# Fri3d_2026_Keeb_00.net
KiCad netlist of a schematic drawn in Altium Designer
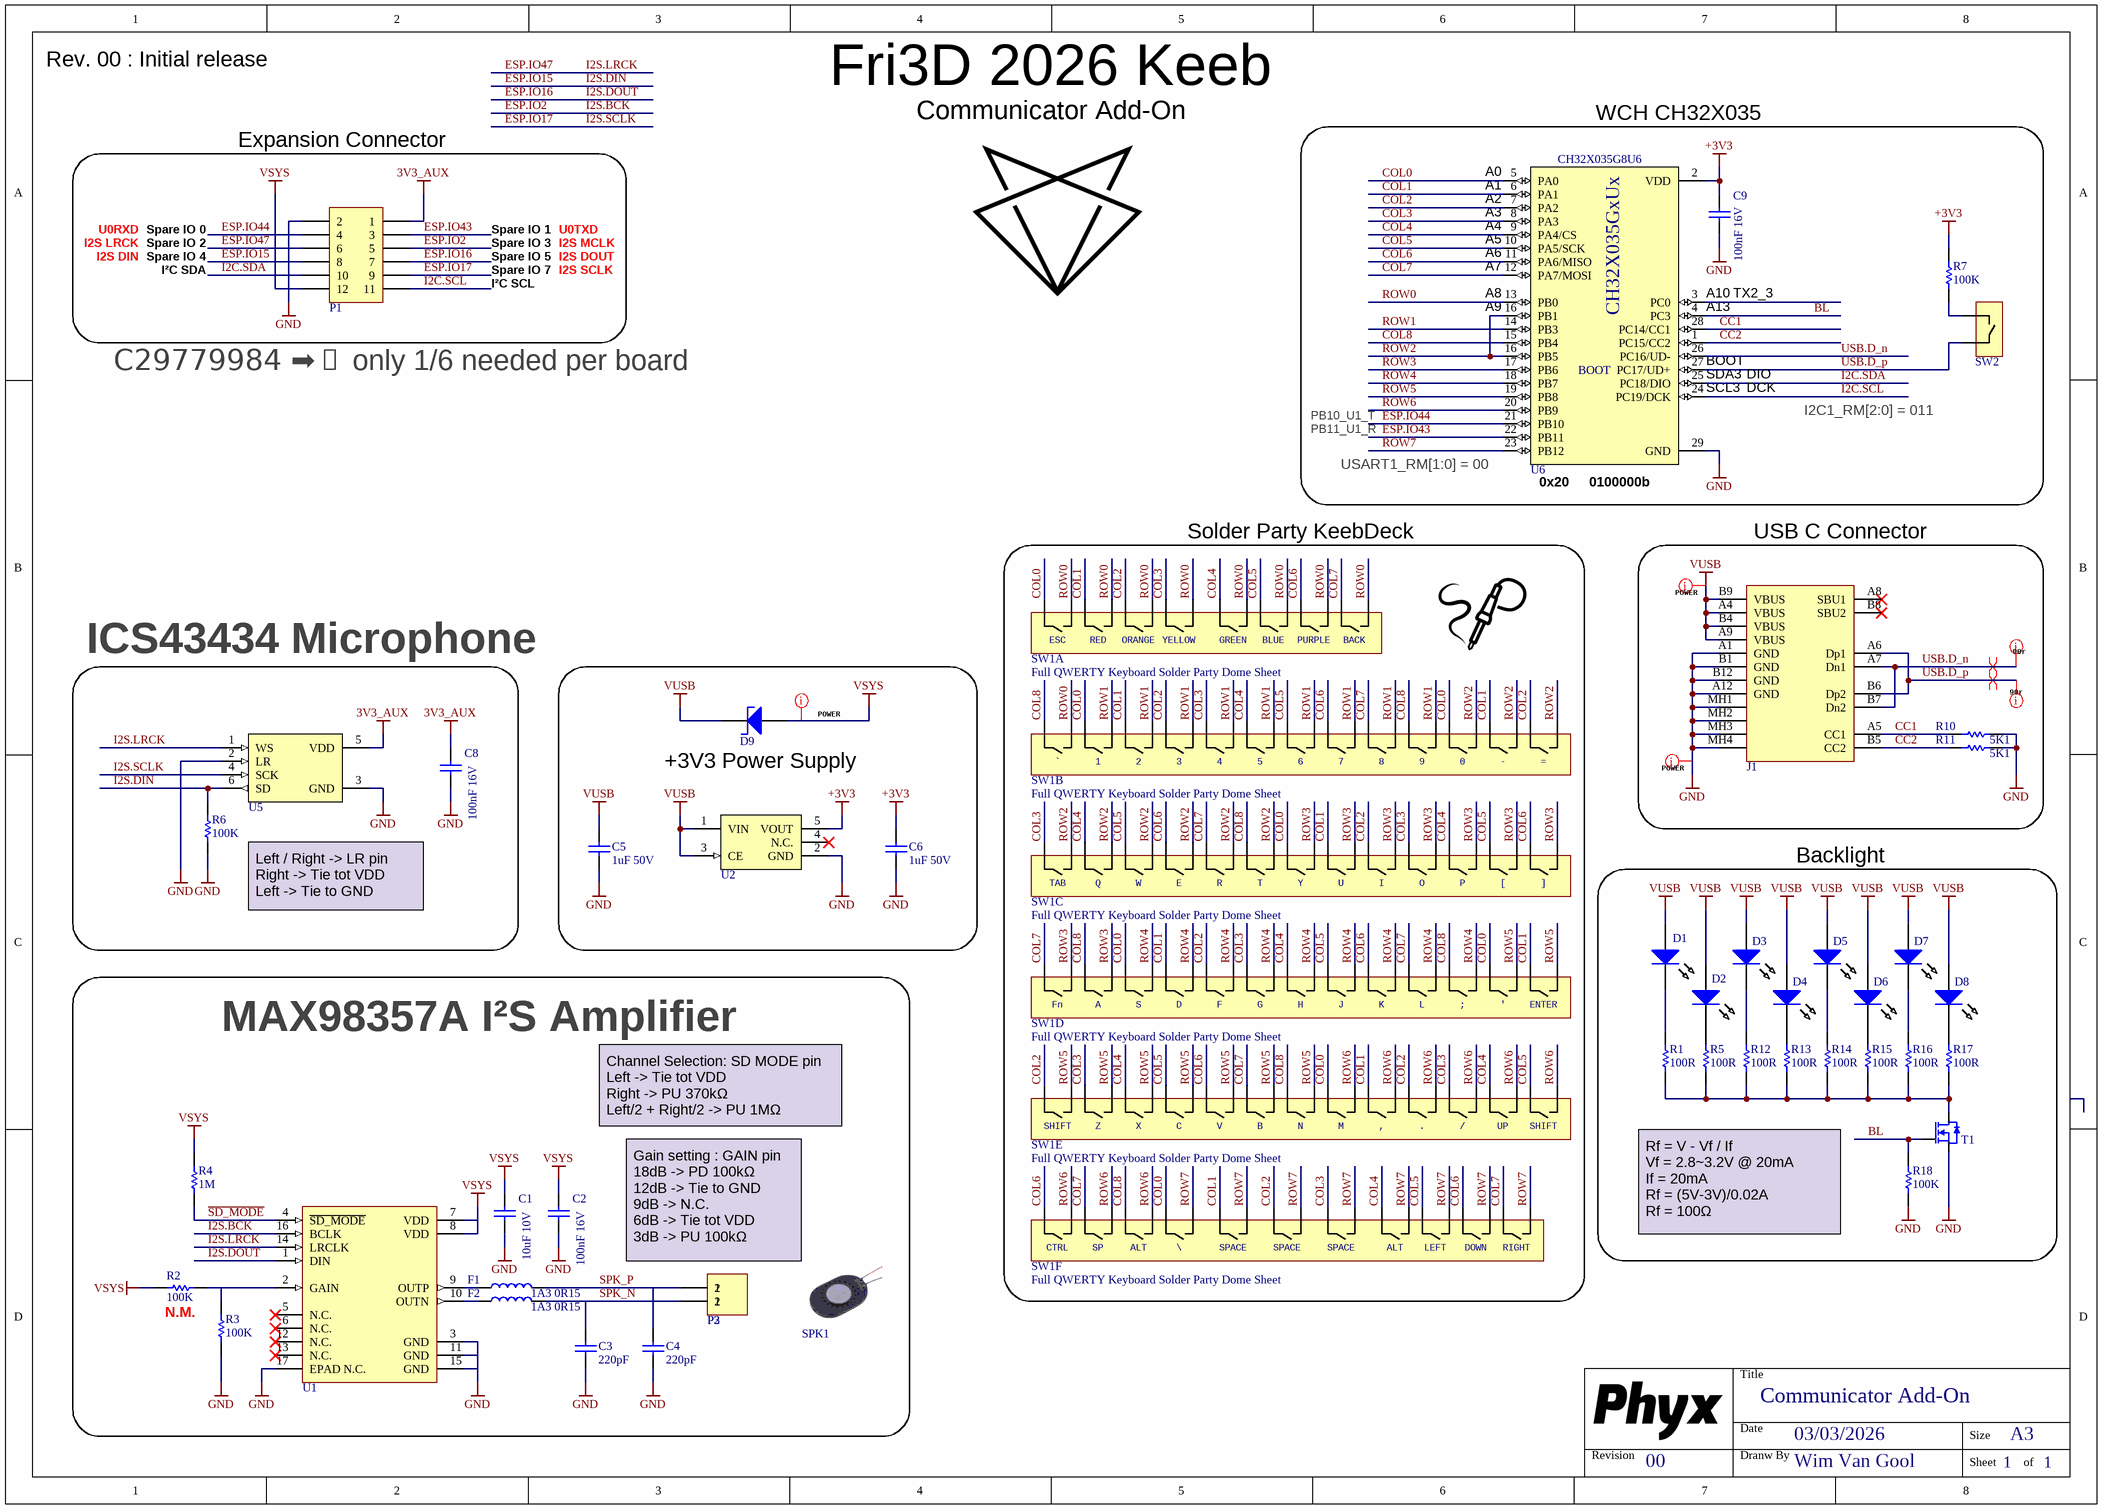
[diagram p0: Fri3d_2026_Keeb_00.SchDoc]

(export (version "E")
  (design (tool "Eeschema 10.0.6"))
  (components
    (comp (ref "C1")
      (value "10uF 10V")
      (footprint "C0805_N")
      (description "Capacitor Ceramic")
      (fields (field (name "Comment") "CAP_CERAMIC"))
      (libsource (lib "Phyx_Components") (part "CAP_CERAMIC"))
    )
    (comp (ref "C2")
      (value "100nF 16V")
      (footprint "C0603_N")
      (description "Capacitor Ceramic")
      (libsource (lib "Phyx_Components") (part "CAP_CERAMIC"))
    )
    (comp (ref "C3")
      (value "220pF")
      (footprint "C0603_N")
      (description "Capacitor Ceramic")
      (fields (field (name "Comment") "CAP_CERAMIC"))
      (libsource (lib "Phyx_Components") (part "CAP_CERAMIC"))
    )
    (comp (ref "C4")
      (value "220pF")
      (footprint "C0603_N")
      (description "Capacitor Ceramic")
      (fields (field (name "Comment") "CAP_CERAMIC"))
      (libsource (lib "Phyx_Components") (part "CAP_CERAMIC"))
    )
    (comp (ref "C5")
      (value "1uF 50V")
      (footprint "C0603_N")
      (description "Capacitor Ceramic")
      (fields (field (name "Comment") "CAP_CERAMIC"))
      (libsource (lib "Phyx_Components") (part "CAP_CERAMIC"))
    )
    (comp (ref "C6")
      (value "1uF 50V")
      (footprint "C0603_N")
      (description "Capacitor Ceramic")
      (fields (field (name "Comment") "CAP_CERAMIC"))
      (libsource (lib "Phyx_Components") (part "CAP_CERAMIC"))
    )
    (comp (ref "C8")
      (value "100nF 16V")
      (footprint "C0603_N")
      (description "Capacitor Ceramic")
      (libsource (lib "Phyx_Components") (part "CAP_CERAMIC"))
    )
    (comp (ref "C9")
      (value "100nF 16V")
      (footprint "C0603_N")
      (description "Capacitor Ceramic")
      (libsource (lib "Phyx_Components") (part "CAP_CERAMIC"))
    )
    (comp (ref "D1")
      (value "Side emitting Cool White LED 3.0V 30mA 120° 2900mcd")
      (footprint "LITE_LTW-010DCG")
      (description "=Description")
      (libsource (lib "Phyx_Components") (part "LED_WHITE"))
    )
    (comp (ref "D2")
      (value "Side emitting Cool White LED 3.0V 30mA 120° 2900mcd")
      (footprint "LITE_LTW-010DCG")
      (description "=Description")
      (libsource (lib "Phyx_Components") (part "LED_WHITE"))
    )
    (comp (ref "D3")
      (value "Side emitting Cool White LED 3.0V 30mA 120° 2900mcd")
      (footprint "LITE_LTW-010DCG")
      (description "=Description")
      (libsource (lib "Phyx_Components") (part "LED_WHITE"))
    )
    (comp (ref "D4")
      (value "Side emitting Cool White LED 3.0V 30mA 120° 2900mcd")
      (footprint "LITE_LTW-010DCG")
      (description "=Description")
      (libsource (lib "Phyx_Components") (part "LED_WHITE"))
    )
    (comp (ref "D5")
      (value "Side emitting Cool White LED 3.0V 30mA 120° 2900mcd")
      (footprint "LITE_LTW-010DCG")
      (description "=Description")
      (libsource (lib "Phyx_Components") (part "LED_WHITE"))
    )
    (comp (ref "D6")
      (value "Side emitting Cool White LED 3.0V 30mA 120° 2900mcd")
      (footprint "LITE_LTW-010DCG")
      (description "=Description")
      (libsource (lib "Phyx_Components") (part "LED_WHITE"))
    )
    (comp (ref "D7")
      (value "Side emitting Cool White LED 3.0V 30mA 120° 2900mcd")
      (footprint "LITE_LTW-010DCG")
      (description "=Description")
      (libsource (lib "Phyx_Components") (part "LED_WHITE"))
    )
    (comp (ref "D8")
      (value "Side emitting Cool White LED 3.0V 30mA 120° 2900mcd")
      (footprint "LITE_LTW-010DCG")
      (description "=Description")
      (libsource (lib "Phyx_Components") (part "LED_WHITE"))
    )
    (comp (ref "D9")
      (value "CUS10S30 Schottky Power Rectifier, 1A, 30V")
      (footprint "SOD-323_AC")
      (description "=Description")
      (libsource (lib "Phyx_Components") (part "Schottky_AC"))
    )
    (comp (ref "F1")
      (value "1A3 0R15")
      (footprint "L0603")
      (fields (field (name "Comment") "BLM18KG601SN1D"))
      (libsource (lib "Phyx_Components") (part "FERRITE"))
    )
    (comp (ref "F2")
      (value "1A3 0R15")
      (footprint "L0603")
      (fields (field (name "Comment") "BLM18KG601SN1D"))
      (libsource (lib "Phyx_Components") (part "FERRITE"))
    )
    (comp (ref "J1")
      (value "USB 2.0 C Reversible Receptacle Horizontal full SMD")
      (footprint "XUNPU-TYPEC-304S-ACP16")
      (libsource (lib "Phyx_Components") (part "USB_C_16_4"))
    )
    (comp (ref "P1")
      (value "Header 6X2")
      (footprint "HDR2X6")
      (libsource (lib "Phyx_Components") (part "Header 6X2"))
    )
    (comp (ref "P2")
      (value "Header 2.0mm Shrouded 2")
      (footprint "WE_620102131822")
      (libsource (lib "Phyx_Components") (part "Header 2"))
    )
    (comp (ref "P3") (value "Header 2 RA") (footprint "HDR1X2_RA") (libsource (lib "") (part "Header 2_1")))
    (comp (ref "R1")
      (value "100R")
      (footprint "R0603_N")
      (fields (field (name "Comment") "RESISTOR"))
      (libsource (lib "Phyx_Components") (part "RESISTOR"))
    )
    (comp (ref "R2")
      (value "100K")
      (footprint "R0603_N")
      (fields (field (name "Comment") "RESISTOR"))
      (libsource (lib "Phyx_Components") (part "RESISTOR"))
    )
    (comp (ref "R3")
      (value "100K")
      (footprint "R0603_N")
      (fields (field (name "Comment") "RESISTOR"))
      (libsource (lib "Phyx_Components") (part "RESISTOR"))
    )
    (comp (ref "R4")
      (value "1M")
      (footprint "R0603_N")
      (fields (field (name "Comment") "RESISTOR"))
      (libsource (lib "Phyx_Components") (part "RESISTOR"))
    )
    (comp (ref "R5")
      (value "100R")
      (footprint "R0603_N")
      (fields (field (name "Comment") "RESISTOR"))
      (libsource (lib "Phyx_Components") (part "RESISTOR"))
    )
    (comp (ref "R6")
      (value "100K")
      (footprint "R0603_N")
      (fields (field (name "Comment") "RESISTOR"))
      (libsource (lib "Phyx_Components") (part "RESISTOR"))
    )
    (comp (ref "R7")
      (value "100K")
      (footprint "R0603_N")
      (fields (field (name "Comment") "RESISTOR"))
      (libsource (lib "Phyx_Components") (part "RESISTOR"))
    )
    (comp (ref "R10")
      (value "5K1")
      (footprint "R0603_N")
      (fields (field (name "Comment") "RESISTOR"))
      (libsource (lib "Phyx_Components") (part "RESISTOR"))
    )
    (comp (ref "R11")
      (value "5K1")
      (footprint "R0603_N")
      (fields (field (name "Comment") "RESISTOR"))
      (libsource (lib "Phyx_Components") (part "RESISTOR"))
    )
    (comp (ref "R12")
      (value "100R")
      (footprint "R0603_N")
      (fields (field (name "Comment") "RESISTOR"))
      (libsource (lib "Phyx_Components") (part "RESISTOR"))
    )
    (comp (ref "R13")
      (value "100R")
      (footprint "R0603_N")
      (fields (field (name "Comment") "RESISTOR"))
      (libsource (lib "Phyx_Components") (part "RESISTOR"))
    )
    (comp (ref "R14")
      (value "100R")
      (footprint "R0603_N")
      (fields (field (name "Comment") "RESISTOR"))
      (libsource (lib "Phyx_Components") (part "RESISTOR"))
    )
    (comp (ref "R15")
      (value "100R")
      (footprint "R0603_N")
      (fields (field (name "Comment") "RESISTOR"))
      (libsource (lib "Phyx_Components") (part "RESISTOR"))
    )
    (comp (ref "R16")
      (value "100R")
      (footprint "R0603_N")
      (fields (field (name "Comment") "RESISTOR"))
      (libsource (lib "Phyx_Components") (part "RESISTOR"))
    )
    (comp (ref "R17")
      (value "100R")
      (footprint "R0603_N")
      (fields (field (name "Comment") "RESISTOR"))
      (libsource (lib "Phyx_Components") (part "RESISTOR"))
    )
    (comp (ref "R18")
      (value "100K")
      (footprint "R0603_N")
      (fields (field (name "Comment") "RESISTOR"))
      (libsource (lib "Phyx_Components") (part "RESISTOR"))
    )
    (comp (ref "SPK1")
      (value "INGHAi GSPK3020035PN 8R 1W 100mm Leads")
      (libsource (lib "Phyx_Components") (part "GSPK3020035PN"))
    )
    (comp (ref "SW1")
      (value "Full QWERTY Keyboard Solder Party Dome Sheet")
      (footprint "Solder_Party_Keyb")
      (libsource (lib "CONNECTORS") (part "Solder_Party_Keyb"))
    )
    (comp (ref "SW2")
      (value "4.5x4.5mm tact SMD H3,8mm")
      (footprint "WE_430181038816")
      (libsource (lib "Phyx_Components") (part "SW_TACT"))
    )
    (comp (ref "T1")
      (value "0.2A N-Ch MOSFET Vgs 1.5")
      (footprint "SOT23-3")
      (libsource (lib "Phyx_Components") (part "N_MOSFET_GSD"))
    )
    (comp (ref "U1")
      (value "Mono I²S DAC AMP 3W 2.5~5.5V")
      (footprint "QFN_16_0.5_3X3")
      (description "=Description")
      (libsource (lib "Phyx_Components") (part "ADI_MAX98357_QFN"))
    )
    (comp (ref "U2")
      (value "3V3 LDO 300mA 150mV")
      (footprint "SOT23-5")
      (description "=Designator")
      (libsource (lib "Phyx_Components") (part "XC6210_SOT"))
    )
    (comp (ref "U5")
      (value "I2S MIC ICS-43434")
      (footprint "TDK_ICS-43434")
      (description "=Description")
      (libsource (lib "Phyx_Components") (part "TDK_ICS-43434"))
    )
    (comp (ref "U6")
      (value "CH32X035G8U6")
      (footprint "QFN_28_4.0x4.0_P0.4")
      (fields
        (field (name "Comment") "WCH CH32X035G8U6 QFN28 RISC-V 32-bit MCU, 62KB Flash, 10KB RAM, USB PD")
      )
      (libsource (lib "Phyx_Components") (part "WCH_CH32X035GxUx"))
    )
  )
  (nets
    (net (code "1") (name "+3V3") (class "Default")
      (node (ref "C6") (pin "1") (pinfunction "1_1") (pintype "passive"))
      (node (ref "C9") (pin "1") (pinfunction "1_1") (pintype "passive"))
      (node (ref "R7") (pin "1") (pinfunction "1_1") (pintype "passive"))
      (node (ref "U2") (pin "5") (pinfunction "VOUT_5") (pintype "power_in"))
      (node (ref "U6") (pin "2") (pinfunction "VDD_2") (pintype "power_in"))
    )
    (net (code "2") (name "/BL") (class "Default")
      (node (ref "R18") (pin "1") (pinfunction "1_1") (pintype "passive"))
      (node (ref "T1") (pin "1") (pinfunction "G_1") (pintype "passive"))
      (node (ref "U6") (pin "4") (pinfunction "PC3_4") (pintype "bidirectional"))
    )
    (net (code "3") (name "/CC1") (class "Default")
      (node (ref "J1") (pin "A5") (pinfunction "CC1_A5") (pintype "passive"))
      (node (ref "R10") (pin "1") (pinfunction "1_1") (pintype "passive"))
      (node (ref "U6") (pin "28") (pinfunction "PC14/CC1_28") (pintype "bidirectional"))
    )
    (net (code "4") (name "/CC2") (class "Default")
      (node (ref "J1") (pin "B5") (pinfunction "CC2_B5") (pintype "passive"))
      (node (ref "R11") (pin "1") (pinfunction "1_1") (pintype "passive"))
      (node (ref "U6") (pin "1") (pinfunction "PC15/CC2_1") (pintype "bidirectional"))
    )
    (net (code "5") (name "/COL0") (class "Default")
      (node (ref "SW1") (pin "1") (pinfunction "1_1") (pintype "passive"))
      (node (ref "SW1") (pin "109") (pinfunction "109_109") (pintype "passive"))
      (node (ref "SW1") (pin "127") (pinfunction "127_127") (pintype "passive"))
      (node (ref "SW1") (pin "19") (pinfunction "19_19") (pintype "passive"))
      (node (ref "SW1") (pin "37") (pinfunction "37_37") (pintype "passive"))
      (node (ref "SW1") (pin "55") (pinfunction "55_55") (pintype "passive"))
      (node (ref "SW1") (pin "73") (pinfunction "73_73") (pintype "passive"))
      (node (ref "SW1") (pin "91") (pinfunction "91_91") (pintype "passive"))
      (node (ref "U6") (pin "5") (pinfunction "PA0_5") (pintype "bidirectional"))
    )
    (net (code "6") (name "/COL1") (class "Default")
      (node (ref "SW1") (pin "111") (pinfunction "111_111") (pintype "passive"))
      (node (ref "SW1") (pin "129") (pinfunction "129_129") (pintype "passive"))
      (node (ref "SW1") (pin "21") (pinfunction "21_21") (pintype "passive"))
      (node (ref "SW1") (pin "3") (pinfunction "3_3") (pintype "passive"))
      (node (ref "SW1") (pin "39") (pinfunction "39_39") (pintype "passive"))
      (node (ref "SW1") (pin "57") (pinfunction "57_57") (pintype "passive"))
      (node (ref "SW1") (pin "75") (pinfunction "75_75") (pintype "passive"))
      (node (ref "SW1") (pin "93") (pinfunction "93_93") (pintype "passive"))
      (node (ref "U6") (pin "6") (pinfunction "PA1_6") (pintype "bidirectional"))
    )
    (net (code "7") (name "/COL2") (class "Default")
      (node (ref "SW1") (pin "113") (pinfunction "113_113") (pintype "passive"))
      (node (ref "SW1") (pin "131") (pinfunction "131_131") (pintype "passive"))
      (node (ref "SW1") (pin "23") (pinfunction "23_23") (pintype "passive"))
      (node (ref "SW1") (pin "41") (pinfunction "41_41") (pintype "passive"))
      (node (ref "SW1") (pin "5") (pinfunction "5_5") (pintype "passive"))
      (node (ref "SW1") (pin "59") (pinfunction "59_59") (pintype "passive"))
      (node (ref "SW1") (pin "77") (pinfunction "77_77") (pintype "passive"))
      (node (ref "SW1") (pin "95") (pinfunction "95_95") (pintype "passive"))
      (node (ref "U6") (pin "7") (pinfunction "PA2_7") (pintype "bidirectional"))
    )
    (net (code "8") (name "/COL3") (class "Default")
      (node (ref "SW1") (pin "115") (pinfunction "115_115") (pintype "passive"))
      (node (ref "SW1") (pin "133") (pinfunction "133_133") (pintype "passive"))
      (node (ref "SW1") (pin "25") (pinfunction "25_25") (pintype "passive"))
      (node (ref "SW1") (pin "43") (pinfunction "43_43") (pintype "passive"))
      (node (ref "SW1") (pin "61") (pinfunction "61_61") (pintype "passive"))
      (node (ref "SW1") (pin "7") (pinfunction "7_7") (pintype "passive"))
      (node (ref "SW1") (pin "79") (pinfunction "79_79") (pintype "passive"))
      (node (ref "SW1") (pin "97") (pinfunction "97_97") (pintype "passive"))
      (node (ref "U6") (pin "8") (pinfunction "PA3_8") (pintype "bidirectional"))
    )
    (net (code "9") (name "/COL4") (class "Default")
      (node (ref "SW1") (pin "117") (pinfunction "117_117") (pintype "passive"))
      (node (ref "SW1") (pin "135") (pinfunction "135_135") (pintype "passive"))
      (node (ref "SW1") (pin "27") (pinfunction "27_27") (pintype "passive"))
      (node (ref "SW1") (pin "45") (pinfunction "45_45") (pintype "passive"))
      (node (ref "SW1") (pin "63") (pinfunction "63_63") (pintype "passive"))
      (node (ref "SW1") (pin "81") (pinfunction "81_81") (pintype "passive"))
      (node (ref "SW1") (pin "9") (pinfunction "9_9") (pintype "passive"))
      (node (ref "SW1") (pin "99") (pinfunction "99_99") (pintype "passive"))
      (node (ref "U6") (pin "9") (pinfunction "PA4/CS_9") (pintype "bidirectional"))
    )
    (net (code "10") (name "/COL5") (class "Default")
      (node (ref "SW1") (pin "101") (pinfunction "101_101") (pintype "passive"))
      (node (ref "SW1") (pin "11") (pinfunction "11_11") (pintype "passive"))
      (node (ref "SW1") (pin "119") (pinfunction "119_119") (pintype "passive"))
      (node (ref "SW1") (pin "137") (pinfunction "137_137") (pintype "passive"))
      (node (ref "SW1") (pin "29") (pinfunction "29_29") (pintype "passive"))
      (node (ref "SW1") (pin "47") (pinfunction "47_47") (pintype "passive"))
      (node (ref "SW1") (pin "65") (pinfunction "65_65") (pintype "passive"))
      (node (ref "SW1") (pin "83") (pinfunction "83_83") (pintype "passive"))
      (node (ref "U6") (pin "10") (pinfunction "PA5/SCK_10") (pintype "bidirectional"))
    )
    (net (code "11") (name "/COL6") (class "Default")
      (node (ref "SW1") (pin "103") (pinfunction "103_103") (pintype "passive"))
      (node (ref "SW1") (pin "121") (pinfunction "121_121") (pintype "passive"))
      (node (ref "SW1") (pin "13") (pinfunction "13_13") (pintype "passive"))
      (node (ref "SW1") (pin "139") (pinfunction "139_139") (pintype "passive"))
      (node (ref "SW1") (pin "31") (pinfunction "31_31") (pintype "passive"))
      (node (ref "SW1") (pin "49") (pinfunction "49_49") (pintype "passive"))
      (node (ref "SW1") (pin "67") (pinfunction "67_67") (pintype "passive"))
      (node (ref "SW1") (pin "85") (pinfunction "85_85") (pintype "passive"))
      (node (ref "U6") (pin "11") (pinfunction "PA6/MISO_11") (pintype "bidirectional"))
    )
    (net (code "12") (name "/COL7") (class "Default")
      (node (ref "SW1") (pin "105") (pinfunction "105_105") (pintype "passive"))
      (node (ref "SW1") (pin "123") (pinfunction "123_123") (pintype "passive"))
      (node (ref "SW1") (pin "141") (pinfunction "141_141") (pintype "passive"))
      (node (ref "SW1") (pin "15") (pinfunction "15_15") (pintype "passive"))
      (node (ref "SW1") (pin "33") (pinfunction "33_33") (pintype "passive"))
      (node (ref "SW1") (pin "51") (pinfunction "51_51") (pintype "passive"))
      (node (ref "SW1") (pin "69") (pinfunction "69_69") (pintype "passive"))
      (node (ref "SW1") (pin "87") (pinfunction "87_87") (pintype "passive"))
      (node (ref "U6") (pin "12") (pinfunction "PA7/MOSI_12") (pintype "bidirectional"))
    )
    (net (code "13") (name "/COL8") (class "Default")
      (node (ref "SW1") (pin "107") (pinfunction "107_107") (pintype "passive"))
      (node (ref "SW1") (pin "125") (pinfunction "125_125") (pintype "passive"))
      (node (ref "SW1") (pin "17") (pinfunction "17_17") (pintype "passive"))
      (node (ref "SW1") (pin "35") (pinfunction "35_35") (pintype "passive"))
      (node (ref "SW1") (pin "53") (pinfunction "53_53") (pintype "passive"))
      (node (ref "SW1") (pin "71") (pinfunction "71_71") (pintype "passive"))
      (node (ref "SW1") (pin "89") (pinfunction "89_89") (pintype "passive"))
      (node (ref "U6") (pin "15") (pinfunction "PB4_15") (pintype "bidirectional"))
    )
    (net (code "14") (name "/ESP.IO2") (class "Default")
      (node (ref "P1") (pin "5") (pinfunction "5_5") (pintype "passive"))
      (node (ref "U1") (pin "16") (pinfunction "BCLK_16") (pintype "input"))
    )
    (net (code "15") (name "/ESP.IO15") (class "Default")
      (node (ref "P1") (pin "8") (pinfunction "8_8") (pintype "passive"))
      (node (ref "R6") (pin "1") (pinfunction "1_1") (pintype "passive"))
      (node (ref "U5") (pin "6") (pinfunction "SD_6") (pintype "output"))
    )
    (net (code "16") (name "/ESP.IO16") (class "Default")
      (node (ref "P1") (pin "7") (pinfunction "7_7") (pintype "passive"))
      (node (ref "U1") (pin "1") (pinfunction "DIN_1") (pintype "input"))
    )
    (net (code "17") (name "/ESP.IO17") (class "Default")
      (node (ref "P1") (pin "9") (pinfunction "9_9") (pintype "passive"))
      (node (ref "U5") (pin "4") (pinfunction "SCK_4") (pintype "input"))
    )
    (net (code "18") (name "/ESP.IO43") (class "Default")
      (node (ref "P1") (pin "3") (pinfunction "3_3") (pintype "passive"))
      (node (ref "U6") (pin "22") (pinfunction "PB11_22") (pintype "bidirectional"))
    )
    (net (code "19") (name "/ESP.IO44") (class "Default")
      (node (ref "P1") (pin "4") (pinfunction "4_4") (pintype "passive"))
      (node (ref "U6") (pin "21") (pinfunction "PB10_21") (pintype "bidirectional"))
    )
    (net (code "20") (name "/ESP.IO47") (class "Default")
      (node (ref "P1") (pin "6") (pinfunction "6_6") (pintype "passive"))
      (node (ref "U1") (pin "14") (pinfunction "LRCLK_14") (pintype "input"))
      (node (ref "U5") (pin "1") (pinfunction "WS_1") (pintype "input"))
    )
    (net (code "21") (name "/I2C.SCL") (class "Default")
      (node (ref "P1") (pin "11") (pinfunction "11_11") (pintype "passive"))
      (node (ref "U6") (pin "24") (pinfunction "PC19/DCK_24") (pintype "bidirectional"))
    )
    (net (code "22") (name "/I2C.SDA") (class "Default")
      (node (ref "P1") (pin "10") (pinfunction "10_10") (pintype "passive"))
      (node (ref "U6") (pin "25") (pinfunction "PC18/DIO_25") (pintype "bidirectional"))
    )
    (net (code "23") (name "/ROW0") (class "Default")
      (node (ref "SW1") (pin "10") (pinfunction "10_10") (pintype "passive"))
      (node (ref "SW1") (pin "12") (pinfunction "12_12") (pintype "passive"))
      (node (ref "SW1") (pin "14") (pinfunction "14_14") (pintype "passive"))
      (node (ref "SW1") (pin "16") (pinfunction "16_16") (pintype "passive"))
      (node (ref "SW1") (pin "18") (pinfunction "18_18") (pintype "passive"))
      (node (ref "SW1") (pin "2") (pinfunction "2_2") (pintype "passive"))
      (node (ref "SW1") (pin "4") (pinfunction "4_4") (pintype "passive"))
      (node (ref "SW1") (pin "6") (pinfunction "6_6") (pintype "passive"))
      (node (ref "SW1") (pin "8") (pinfunction "8_8") (pintype "passive"))
      (node (ref "U6") (pin "13") (pinfunction "PB0_13") (pintype "bidirectional"))
    )
    (net (code "24") (name "/ROW1") (class "Default")
      (node (ref "SW1") (pin "20") (pinfunction "20_20") (pintype "passive"))
      (node (ref "SW1") (pin "22") (pinfunction "22_22") (pintype "passive"))
      (node (ref "SW1") (pin "24") (pinfunction "24_24") (pintype "passive"))
      (node (ref "SW1") (pin "26") (pinfunction "26_26") (pintype "passive"))
      (node (ref "SW1") (pin "28") (pinfunction "28_28") (pintype "passive"))
      (node (ref "SW1") (pin "30") (pinfunction "30_30") (pintype "passive"))
      (node (ref "SW1") (pin "32") (pinfunction "32_32") (pintype "passive"))
      (node (ref "SW1") (pin "34") (pinfunction "34_34") (pintype "passive"))
      (node (ref "SW1") (pin "36") (pinfunction "36_36") (pintype "passive"))
      (node (ref "U6") (pin "14") (pinfunction "PB3_14") (pintype "bidirectional"))
    )
    (net (code "25") (name "/ROW2") (class "Default")
      (node (ref "SW1") (pin "38") (pinfunction "38_38") (pintype "passive"))
      (node (ref "SW1") (pin "40") (pinfunction "40_40") (pintype "passive"))
      (node (ref "SW1") (pin "42") (pinfunction "42_42") (pintype "passive"))
      (node (ref "SW1") (pin "44") (pinfunction "44_44") (pintype "passive"))
      (node (ref "SW1") (pin "46") (pinfunction "46_46") (pintype "passive"))
      (node (ref "SW1") (pin "48") (pinfunction "48_48") (pintype "passive"))
      (node (ref "SW1") (pin "50") (pinfunction "50_50") (pintype "passive"))
      (node (ref "SW1") (pin "52") (pinfunction "52_52") (pintype "passive"))
      (node (ref "SW1") (pin "54") (pinfunction "54_54") (pintype "passive"))
      (node (ref "U6") (pin "16") (pinfunction "PB1_16") (pintype "bidirectional"))
    )
    (net (code "26") (name "/ROW3") (class "Default")
      (node (ref "SW1") (pin "56") (pinfunction "56_56") (pintype "passive"))
      (node (ref "SW1") (pin "58") (pinfunction "58_58") (pintype "passive"))
      (node (ref "SW1") (pin "60") (pinfunction "60_60") (pintype "passive"))
      (node (ref "SW1") (pin "62") (pinfunction "62_62") (pintype "passive"))
      (node (ref "SW1") (pin "64") (pinfunction "64_64") (pintype "passive"))
      (node (ref "SW1") (pin "66") (pinfunction "66_66") (pintype "passive"))
      (node (ref "SW1") (pin "68") (pinfunction "68_68") (pintype "passive"))
      (node (ref "SW1") (pin "70") (pinfunction "70_70") (pintype "passive"))
      (node (ref "SW1") (pin "72") (pinfunction "72_72") (pintype "passive"))
      (node (ref "U6") (pin "17") (pinfunction "PB6_17") (pintype "bidirectional"))
    )
    (net (code "27") (name "/ROW4") (class "Default")
      (node (ref "SW1") (pin "74") (pinfunction "74_74") (pintype "passive"))
      (node (ref "SW1") (pin "76") (pinfunction "76_76") (pintype "passive"))
      (node (ref "SW1") (pin "78") (pinfunction "78_78") (pintype "passive"))
      (node (ref "SW1") (pin "80") (pinfunction "80_80") (pintype "passive"))
      (node (ref "SW1") (pin "82") (pinfunction "82_82") (pintype "passive"))
      (node (ref "SW1") (pin "84") (pinfunction "84_84") (pintype "passive"))
      (node (ref "SW1") (pin "86") (pinfunction "86_86") (pintype "passive"))
      (node (ref "SW1") (pin "88") (pinfunction "88_88") (pintype "passive"))
      (node (ref "SW1") (pin "90") (pinfunction "90_90") (pintype "passive"))
      (node (ref "U6") (pin "18") (pinfunction "PB7_18") (pintype "bidirectional"))
    )
    (net (code "28") (name "/ROW5") (class "Default")
      (node (ref "SW1") (pin "100") (pinfunction "100_100") (pintype "passive"))
      (node (ref "SW1") (pin "102") (pinfunction "102_102") (pintype "passive"))
      (node (ref "SW1") (pin "104") (pinfunction "104_104") (pintype "passive"))
      (node (ref "SW1") (pin "106") (pinfunction "106_106") (pintype "passive"))
      (node (ref "SW1") (pin "108") (pinfunction "108_108") (pintype "passive"))
      (node (ref "SW1") (pin "92") (pinfunction "92_92") (pintype "passive"))
      (node (ref "SW1") (pin "94") (pinfunction "94_94") (pintype "passive"))
      (node (ref "SW1") (pin "96") (pinfunction "96_96") (pintype "passive"))
      (node (ref "SW1") (pin "98") (pinfunction "98_98") (pintype "passive"))
      (node (ref "U6") (pin "19") (pinfunction "PB8_19") (pintype "bidirectional"))
    )
    (net (code "29") (name "/ROW6") (class "Default")
      (node (ref "SW1") (pin "110") (pinfunction "110_110") (pintype "passive"))
      (node (ref "SW1") (pin "112") (pinfunction "112_112") (pintype "passive"))
      (node (ref "SW1") (pin "114") (pinfunction "114_114") (pintype "passive"))
      (node (ref "SW1") (pin "116") (pinfunction "116_116") (pintype "passive"))
      (node (ref "SW1") (pin "118") (pinfunction "118_118") (pintype "passive"))
      (node (ref "SW1") (pin "120") (pinfunction "120_120") (pintype "passive"))
      (node (ref "SW1") (pin "122") (pinfunction "122_122") (pintype "passive"))
      (node (ref "SW1") (pin "124") (pinfunction "124_124") (pintype "passive"))
      (node (ref "SW1") (pin "126") (pinfunction "126_126") (pintype "passive"))
      (node (ref "U6") (pin "20") (pinfunction "PB9_20") (pintype "bidirectional"))
    )
    (net (code "30") (name "/ROW7") (class "Default")
      (node (ref "SW1") (pin "128") (pinfunction "128_128") (pintype "passive"))
      (node (ref "SW1") (pin "130") (pinfunction "130_130") (pintype "passive"))
      (node (ref "SW1") (pin "132") (pinfunction "132_132") (pintype "passive"))
      (node (ref "SW1") (pin "134") (pinfunction "134_134") (pintype "passive"))
      (node (ref "SW1") (pin "136") (pinfunction "136_136") (pintype "passive"))
      (node (ref "SW1") (pin "138") (pinfunction "138_138") (pintype "passive"))
      (node (ref "SW1") (pin "140") (pinfunction "140_140") (pintype "passive"))
      (node (ref "SW1") (pin "142") (pinfunction "142_142") (pintype "passive"))
      (node (ref "U6") (pin "23") (pinfunction "PB12_23") (pintype "bidirectional"))
    )
    (net (code "31") (name "/SPK_N") (class "Default")
      (node (ref "C3") (pin "1") (pinfunction "1_1") (pintype "passive"))
      (node (ref "F2") (pin "2") (pinfunction "2_2") (pintype "passive"))
      (node (ref "P2") (pin "2") (pinfunction "2_2") (pintype "passive"))
      (node (ref "P3") (pin "1") (pinfunction "1_1") (pintype "passive"))
    )
    (net (code "32") (name "/SPK_P") (class "Default")
      (node (ref "C4") (pin "1") (pinfunction "1_1") (pintype "passive"))
      (node (ref "F1") (pin "2") (pinfunction "2_2") (pintype "passive"))
      (node (ref "P2") (pin "1") (pinfunction "1_1") (pintype "passive"))
      (node (ref "P3") (pin "2") (pinfunction "2_2") (pintype "passive"))
    )
    (net (code "33") (name "/USB.D_n") (class "Default")
      (node (ref "J1") (pin "A7") (pinfunction "Dn1_A7") (pintype "passive"))
      (node (ref "J1") (pin "B7") (pinfunction "Dn2_B7") (pintype "passive"))
      (node (ref "U6") (pin "26") (pinfunction "PC16/UD-_26") (pintype "bidirectional"))
    )
    (net (code "34") (name "/USB.D_p") (class "Default")
      (node (ref "J1") (pin "A6") (pinfunction "Dp1_A6") (pintype "passive"))
      (node (ref "J1") (pin "B6") (pinfunction "Dp2_B6") (pintype "passive"))
      (node (ref "SW2") (pin "2") (pinfunction "2_2") (pintype "passive"))
      (node (ref "U6") (pin "27") (pinfunction "PC17/UD+_27") (pintype "bidirectional"))
    )
    (net (code "35") (name "/~{SD_MODE}") (class "Default")
      (node (ref "R4") (pin "2") (pinfunction "2_2") (pintype "passive"))
      (node (ref "U1") (pin "4") (pinfunction "~{SD_MODE}_4") (pintype "input"))
    )
    (net (code "36") (name "3V3_AUX") (class "Default")
      (node (ref "C8") (pin "1") (pinfunction "1_1") (pintype "passive"))
      (node (ref "P1") (pin "1") (pinfunction "1_1") (pintype "passive"))
      (node (ref "U5") (pin "5") (pinfunction "VDD_5") (pintype "power_in"))
    )
    (net (code "37") (name "GND") (class "Default")
      (node (ref "C1") (pin "2") (pinfunction "2_2") (pintype "passive"))
      (node (ref "C2") (pin "2") (pinfunction "2_2") (pintype "passive"))
      (node (ref "C3") (pin "2") (pinfunction "2_2") (pintype "passive"))
      (node (ref "C4") (pin "2") (pinfunction "2_2") (pintype "passive"))
      (node (ref "C5") (pin "2") (pinfunction "2_2") (pintype "passive"))
      (node (ref "C6") (pin "2") (pinfunction "2_2") (pintype "passive"))
      (node (ref "C8") (pin "2") (pinfunction "2_2") (pintype "passive"))
      (node (ref "C9") (pin "2") (pinfunction "2_2") (pintype "passive"))
      (node (ref "J1") (pin "A1") (pinfunction "GND_A1") (pintype "passive"))
      (node (ref "J1") (pin "A12") (pinfunction "GND_A12") (pintype "passive"))
      (node (ref "J1") (pin "B1") (pinfunction "GND_B1") (pintype "passive"))
      (node (ref "J1") (pin "B12") (pinfunction "GND_B12") (pintype "passive"))
      (node (ref "J1") (pin "MH1") (pinfunction "Tab_MH1") (pintype "passive"))
      (node (ref "J1") (pin "MH2") (pinfunction "Tab_MH2") (pintype "passive"))
      (node (ref "J1") (pin "MH3") (pinfunction "Tab_MH3") (pintype "passive"))
      (node (ref "J1") (pin "MH4") (pinfunction "Tab_MH4") (pintype "passive"))
      (node (ref "P1") (pin "2") (pinfunction "2_2") (pintype "passive"))
      (node (ref "R10") (pin "2") (pinfunction "2_2") (pintype "passive"))
      (node (ref "R11") (pin "2") (pinfunction "2_2") (pintype "passive"))
      (node (ref "R18") (pin "2") (pinfunction "2_2") (pintype "passive"))
      (node (ref "R3") (pin "2") (pinfunction "2_2") (pintype "passive"))
      (node (ref "R6") (pin "2") (pinfunction "2_2") (pintype "passive"))
      (node (ref "T1") (pin "2") (pinfunction "S_2") (pintype "passive"))
      (node (ref "U1") (pin "11") (pinfunction "GND_11") (pintype "power_in"))
      (node (ref "U1") (pin "15") (pinfunction "GND_15") (pintype "power_in"))
      (node (ref "U1") (pin "17") (pinfunction "EPAD_N.C._17") (pintype "passive"))
      (node (ref "U1") (pin "3") (pinfunction "GND_3") (pintype "power_in"))
      (node (ref "U2") (pin "2") (pinfunction "GND_2") (pintype "power_in"))
      (node (ref "U5") (pin "2") (pinfunction "LR_2") (pintype "input"))
      (node (ref "U5") (pin "3") (pinfunction "GND_3") (pintype "passive"))
      (node (ref "U6") (pin "29") (pinfunction "GND_29") (pintype "power_in"))
    )
    (net (code "38") (name "Net-(D1-K)") (class "Default")
      (node (ref "D1") (pin "2") (pinfunction "K_2") (pintype "passive"))
      (node (ref "R1") (pin "1") (pinfunction "1_1") (pintype "passive"))
    )
    (net (code "39") (name "Net-(D2-K)") (class "Default")
      (node (ref "D2") (pin "2") (pinfunction "K_2") (pintype "passive"))
      (node (ref "R5") (pin "1") (pinfunction "1_1") (pintype "passive"))
    )
    (net (code "40") (name "Net-(D3-K)") (class "Default")
      (node (ref "D3") (pin "2") (pinfunction "K_2") (pintype "passive"))
      (node (ref "R12") (pin "1") (pinfunction "1_1") (pintype "passive"))
    )
    (net (code "41") (name "Net-(D4-K)") (class "Default")
      (node (ref "D4") (pin "2") (pinfunction "K_2") (pintype "passive"))
      (node (ref "R13") (pin "1") (pinfunction "1_1") (pintype "passive"))
    )
    (net (code "42") (name "Net-(D5-K)") (class "Default")
      (node (ref "D5") (pin "2") (pinfunction "K_2") (pintype "passive"))
      (node (ref "R14") (pin "1") (pinfunction "1_1") (pintype "passive"))
    )
    (net (code "43") (name "Net-(D6-K)") (class "Default")
      (node (ref "D6") (pin "2") (pinfunction "K_2") (pintype "passive"))
      (node (ref "R15") (pin "1") (pinfunction "1_1") (pintype "passive"))
    )
    (net (code "44") (name "Net-(D7-K)") (class "Default")
      (node (ref "D7") (pin "2") (pinfunction "K_2") (pintype "passive"))
      (node (ref "R16") (pin "1") (pinfunction "1_1") (pintype "passive"))
    )
    (net (code "45") (name "Net-(D8-K)") (class "Default")
      (node (ref "D8") (pin "2") (pinfunction "K_2") (pintype "passive"))
      (node (ref "R17") (pin "1") (pinfunction "1_1") (pintype "passive"))
    )
    (net (code "46") (name "Net-(R7-Pad2)") (class "Default")
      (node (ref "R7") (pin "2") (pinfunction "2_2") (pintype "passive"))
      (node (ref "SW2") (pin "1") (pinfunction "1_1") (pintype "passive"))
    )
    (net (code "47") (name "Net-(T1-D)") (class "Default")
      (node (ref "R1") (pin "2") (pinfunction "2_2") (pintype "passive"))
      (node (ref "R12") (pin "2") (pinfunction "2_2") (pintype "passive"))
      (node (ref "R13") (pin "2") (pinfunction "2_2") (pintype "passive"))
      (node (ref "R14") (pin "2") (pinfunction "2_2") (pintype "passive"))
      (node (ref "R15") (pin "2") (pinfunction "2_2") (pintype "passive"))
      (node (ref "R16") (pin "2") (pinfunction "2_2") (pintype "passive"))
      (node (ref "R17") (pin "2") (pinfunction "2_2") (pintype "passive"))
      (node (ref "R5") (pin "2") (pinfunction "2_2") (pintype "passive"))
      (node (ref "T1") (pin "3") (pinfunction "D_3") (pintype "passive"))
    )
    (net (code "48") (name "Net-(U1-GAIN)") (class "Default")
      (node (ref "R2") (pin "1") (pinfunction "1_1") (pintype "passive"))
      (node (ref "R3") (pin "1") (pinfunction "1_1") (pintype "passive"))
      (node (ref "U1") (pin "2") (pinfunction "GAIN_2") (pintype "input"))
    )
    (net (code "49") (name "Net-(U1-OUTN)") (class "Default")
      (node (ref "F2") (pin "1") (pinfunction "1_1") (pintype "passive"))
      (node (ref "U1") (pin "10") (pinfunction "OUTN_10") (pintype "output"))
    )
    (net (code "50") (name "Net-(U1-OUTP)") (class "Default")
      (node (ref "F1") (pin "1") (pinfunction "1_1") (pintype "passive"))
      (node (ref "U1") (pin "9") (pinfunction "OUTP_9") (pintype "output"))
    )
    (net (code "51") (name "VSYS") (class "Default")
      (node (ref "C1") (pin "1") (pinfunction "1_1") (pintype "passive"))
      (node (ref "C2") (pin "1") (pinfunction "1_1") (pintype "passive"))
      (node (ref "D9") (pin "A") (pinfunction "A_A") (pintype "passive"))
      (node (ref "P1") (pin "12") (pinfunction "12_12") (pintype "passive"))
      (node (ref "R2") (pin "2") (pinfunction "2_2") (pintype "passive"))
      (node (ref "R4") (pin "1") (pinfunction "1_1") (pintype "passive"))
      (node (ref "U1") (pin "7") (pinfunction "VDD_7") (pintype "power_in"))
      (node (ref "U1") (pin "8") (pinfunction "VDD_8") (pintype "power_in"))
    )
    (net (code "52") (name "VUSB") (class "Default")
      (node (ref "C5") (pin "1") (pinfunction "1_1") (pintype "passive"))
      (node (ref "D1") (pin "1") (pinfunction "A_1") (pintype "passive"))
      (node (ref "D2") (pin "1") (pinfunction "A_1") (pintype "passive"))
      (node (ref "D3") (pin "1") (pinfunction "A_1") (pintype "passive"))
      (node (ref "D4") (pin "1") (pinfunction "A_1") (pintype "passive"))
      (node (ref "D5") (pin "1") (pinfunction "A_1") (pintype "passive"))
      (node (ref "D6") (pin "1") (pinfunction "A_1") (pintype "passive"))
      (node (ref "D7") (pin "1") (pinfunction "A_1") (pintype "passive"))
      (node (ref "D8") (pin "1") (pinfunction "A_1") (pintype "passive"))
      (node (ref "D9") (pin "C") (pinfunction "C_C") (pintype "passive"))
      (node (ref "J1") (pin "A4") (pinfunction "VBUS_A4") (pintype "passive"))
      (node (ref "J1") (pin "A9") (pinfunction "VBUS_A9") (pintype "passive"))
      (node (ref "J1") (pin "B4") (pinfunction "VBUS_B4") (pintype "passive"))
      (node (ref "J1") (pin "B9") (pinfunction "VBUS_B9") (pintype "passive"))
      (node (ref "U2") (pin "1") (pinfunction "VIN_1") (pintype "power_in"))
      (node (ref "U2") (pin "3") (pinfunction "CE_3") (pintype "input"))
    )
    (net (code "53") (name "unconnected-(J1-SBU1-PadA8)") (class "Default")
      (node (ref "J1") (pin "A8") (pinfunction "SBU1_A8") (pintype "passive+no_connect"))
    )
    (net (code "54") (name "unconnected-(J1-SBU2-PadB8)") (class "Default")
      (node (ref "J1") (pin "B8") (pinfunction "SBU2_B8") (pintype "passive+no_connect"))
    )
    (net (code "55") (name "unconnected-(U1-N.C.-Pad5)") (class "Default")
      (node (ref "U1") (pin "5") (pinfunction "N.C._5") (pintype "passive+no_connect"))
    )
    (net (code "56") (name "unconnected-(U1-N.C.-Pad6)") (class "Default")
      (node (ref "U1") (pin "6") (pinfunction "N.C._6") (pintype "passive+no_connect"))
    )
    (net (code "57") (name "unconnected-(U1-N.C.-Pad12)") (class "Default")
      (node (ref "U1") (pin "12") (pinfunction "N.C._12") (pintype "passive+no_connect"))
    )
    (net (code "58") (name "unconnected-(U1-N.C.-Pad13)") (class "Default")
      (node (ref "U1") (pin "13") (pinfunction "N.C._13") (pintype "passive+no_connect"))
    )
    (net (code "59") (name "unconnected-(U2-N.C.-Pad4)") (class "Default")
      (node (ref "U2") (pin "4") (pinfunction "N.C._4") (pintype "passive+no_connect"))
    )
    (net (code "60") (name "unconnected-(U6-PC0-Pad3)") (class "Default")
      (node (ref "U6") (pin "3") (pinfunction "PC0_3") (pintype "bidirectional"))
    )
  )
)
